# Esp32_Base_Shield.net
KiCad netlist of a schematic drawn in EAGLE
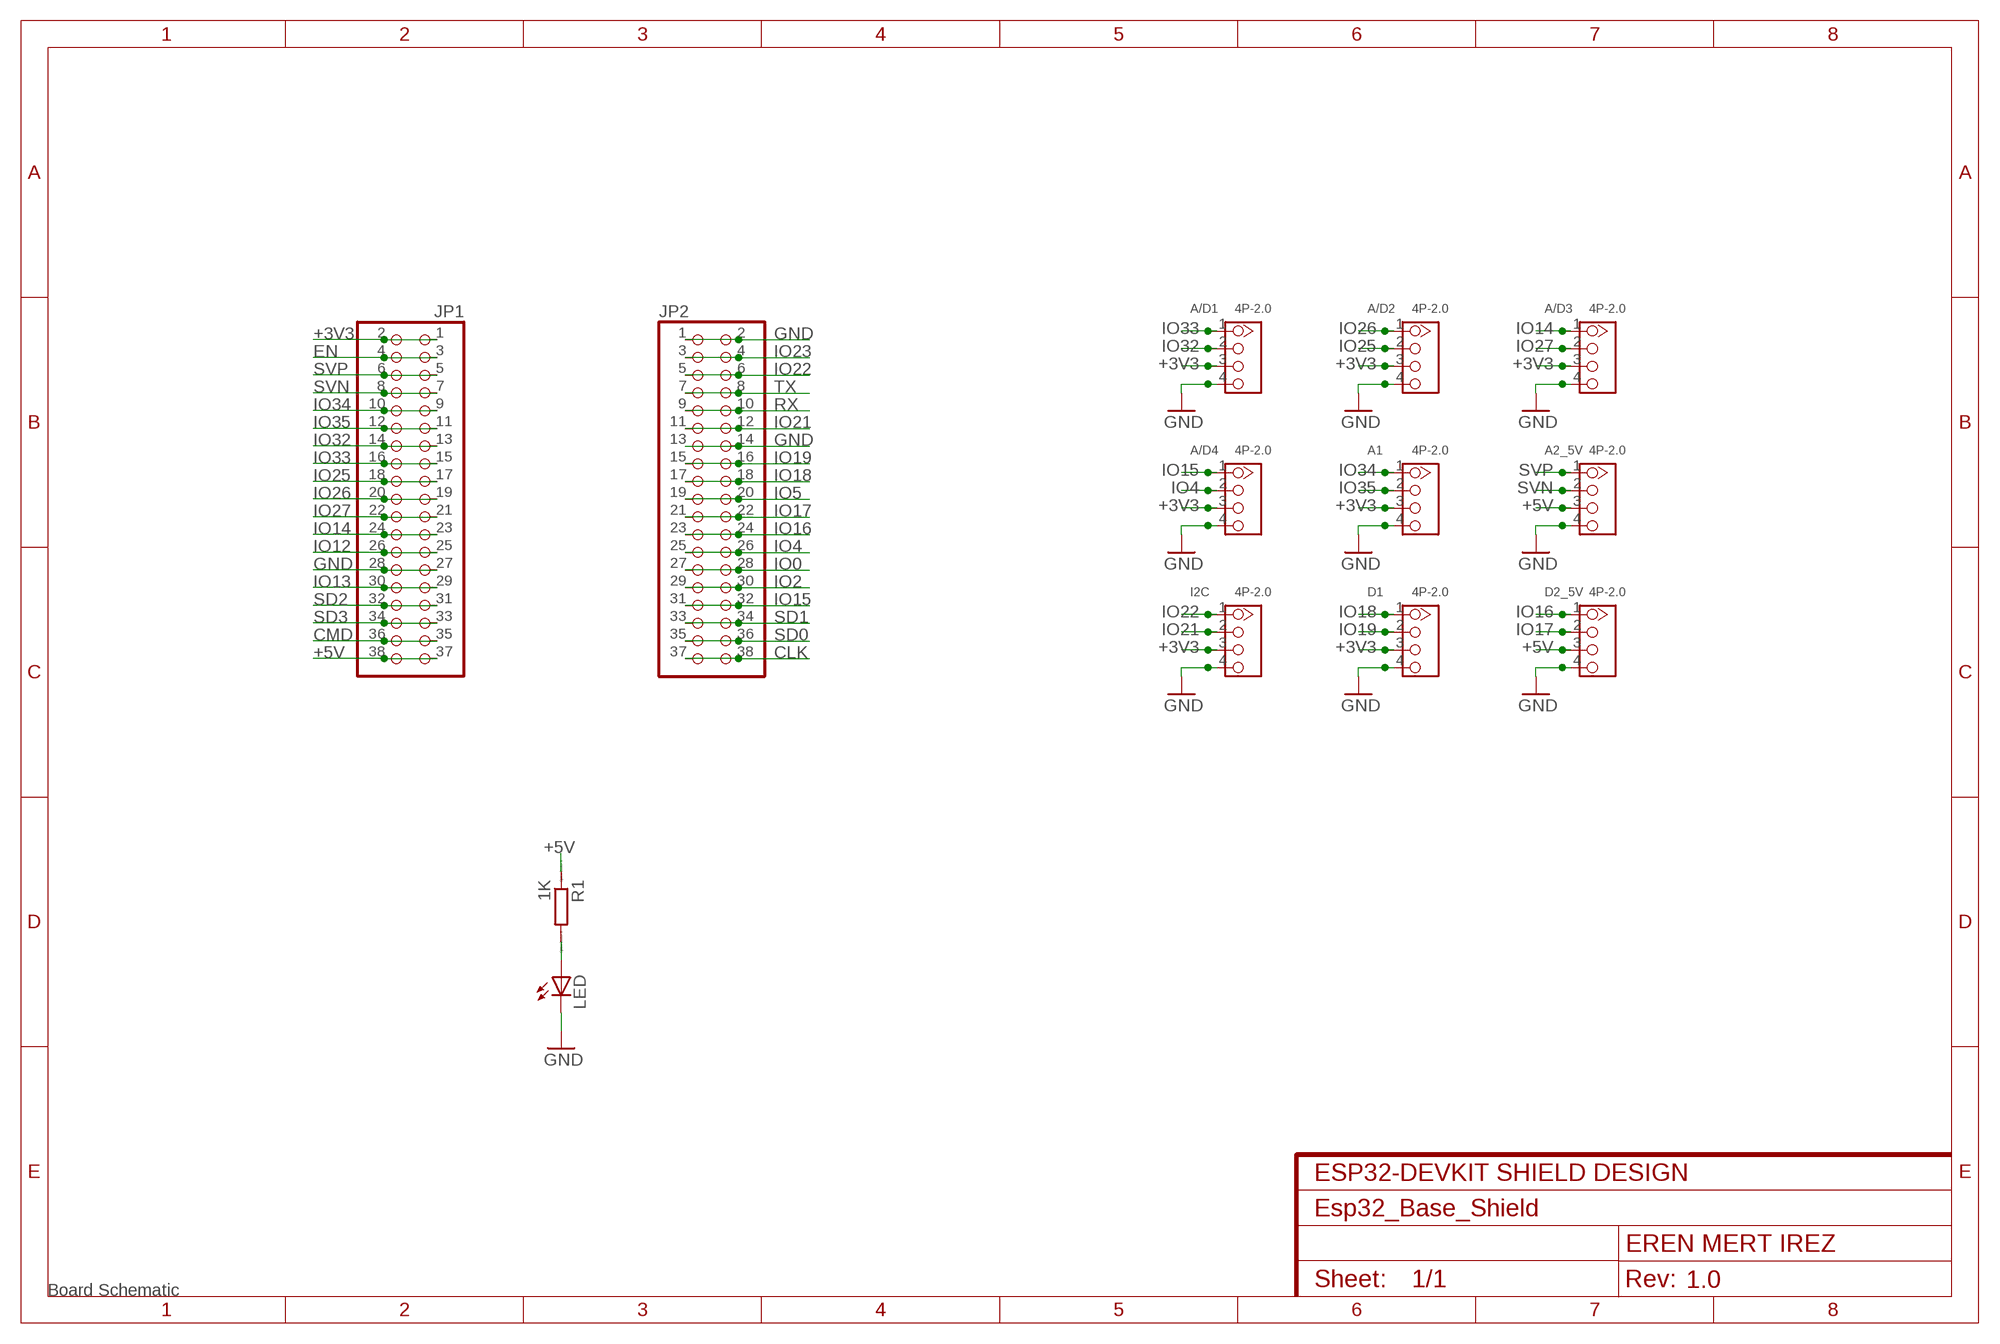
[diagram p0: schematic, sheet 1]

(export (version "E")
  (design (tool "Eeschema 10.0.6"))
  (components
    (comp (ref "A/D1")
      (value "4P-2.0")
      (footprint "eagle-import:HW4-2.0")
      (libsource (lib "eagle-import") (part "GROVE-CONNECTOR-DIP(4P-2.0)"))
    )
    (comp (ref "A/D2")
      (value "4P-2.0")
      (footprint "eagle-import:HW4-2.0")
      (libsource (lib "eagle-import") (part "GROVE-CONNECTOR-DIP(4P-2.0)"))
    )
    (comp (ref "A/D3")
      (value "4P-2.0")
      (footprint "eagle-import:HW4-2.0")
      (libsource (lib "eagle-import") (part "GROVE-CONNECTOR-DIP(4P-2.0)"))
    )
    (comp (ref "A/D4")
      (value "4P-2.0")
      (footprint "eagle-import:HW4-2.0")
      (libsource (lib "eagle-import") (part "GROVE-CONNECTOR-DIP(4P-2.0)"))
    )
    (comp (ref "A1")
      (value "4P-2.0")
      (footprint "eagle-import:HW4-2.0")
      (libsource (lib "eagle-import") (part "GROVE-CONNECTOR-DIP(4P-2.0)"))
    )
    (comp (ref "A2_5V")
      (value "4P-2.0")
      (footprint "eagle-import:HW4-2.0")
      (libsource (lib "eagle-import") (part "GROVE-CONNECTOR-DIP(4P-2.0)"))
    )
    (comp (ref "D1")
      (value "4P-2.0")
      (footprint "eagle-import:HW4-2.0")
      (libsource (lib "eagle-import") (part "GROVE-CONNECTOR-DIP(4P-2.0)"))
    )
    (comp (ref "D2_5V")
      (value "4P-2.0")
      (footprint "eagle-import:HW4-2.0")
      (libsource (lib "eagle-import") (part "GROVE-CONNECTOR-DIP(4P-2.0)"))
    )
    (comp (ref "I2C")
      (value "4P-2.0")
      (footprint "eagle-import:HW4-2.0")
      (libsource (lib "eagle-import") (part "GROVE-CONNECTOR-DIP(4P-2.0)"))
    )
    (comp (ref "JP1")
      (value "PINHD-2X19")
      (footprint "eagle-import:2X19")
      (libsource (lib "eagle-import") (part "PINHD-2X19"))
    )
    (comp (ref "JP2")
      (value "PINHD-2X19")
      (footprint "eagle-import:2X19")
      (libsource (lib "eagle-import") (part "PINHD-2X19"))
    )
    (comp (ref "LED")
      (value "LED3MM")
      (footprint "eagle-import:LED3MM")
      (libsource (lib "eagle-import") (part "LED3MM"))
    )
    (comp (ref "R1")
      (value "1K")
      (footprint "eagle-import:0207_10")
      (libsource (lib "eagle-import") (part "R0207/10"))
    )
  )
  (nets
    (net (code "1") (name "/+3V3") (class "Default")
      (node (ref "A/D1") (pin "3") (pinfunction "3_3") (pintype "bidirectional"))
      (node (ref "A/D2") (pin "3") (pinfunction "3_3") (pintype "bidirectional"))
      (node (ref "A/D3") (pin "3") (pinfunction "3_3") (pintype "bidirectional"))
      (node (ref "A/D4") (pin "3") (pinfunction "3_3") (pintype "bidirectional"))
      (node (ref "A1") (pin "3") (pinfunction "3_3") (pintype "bidirectional"))
      (node (ref "D1") (pin "3") (pinfunction "3_3") (pintype "bidirectional"))
      (node (ref "I2C") (pin "3") (pinfunction "3_3") (pintype "bidirectional"))
      (node (ref "JP1") (pin "1") (pinfunction "1_1") (pintype "passive"))
      (node (ref "JP1") (pin "2") (pinfunction "2_2") (pintype "passive"))
    )
    (net (code "2") (name "/+5V") (class "Default")
      (node (ref "A2_5V") (pin "3") (pinfunction "3_3") (pintype "bidirectional"))
      (node (ref "D2_5V") (pin "3") (pinfunction "3_3") (pintype "bidirectional"))
      (node (ref "JP1") (pin "37") (pinfunction "37_37") (pintype "passive"))
      (node (ref "JP1") (pin "38") (pinfunction "38_38") (pintype "passive"))
      (node (ref "R1") (pin "1") (pinfunction "1_1") (pintype "passive"))
    )
    (net (code "3") (name "/CLK") (class "Default")
      (node (ref "JP2") (pin "37") (pinfunction "37_37") (pintype "passive"))
      (node (ref "JP2") (pin "38") (pinfunction "38_38") (pintype "passive"))
    )
    (net (code "4") (name "/CMD") (class "Default")
      (node (ref "JP1") (pin "35") (pinfunction "35_35") (pintype "passive"))
      (node (ref "JP1") (pin "36") (pinfunction "36_36") (pintype "passive"))
    )
    (net (code "5") (name "/EN") (class "Default")
      (node (ref "JP1") (pin "3") (pinfunction "3_3") (pintype "passive"))
      (node (ref "JP1") (pin "4") (pinfunction "4_4") (pintype "passive"))
    )
    (net (code "6") (name "/IO0") (class "Default")
      (node (ref "JP2") (pin "27") (pinfunction "27_27") (pintype "passive"))
      (node (ref "JP2") (pin "28") (pinfunction "28_28") (pintype "passive"))
    )
    (net (code "7") (name "/IO2") (class "Default")
      (node (ref "JP2") (pin "29") (pinfunction "29_29") (pintype "passive"))
      (node (ref "JP2") (pin "30") (pinfunction "30_30") (pintype "passive"))
    )
    (net (code "8") (name "/IO4") (class "Default")
      (node (ref "A/D4") (pin "2") (pinfunction "2_2") (pintype "bidirectional"))
      (node (ref "JP2") (pin "25") (pinfunction "25_25") (pintype "passive"))
      (node (ref "JP2") (pin "26") (pinfunction "26_26") (pintype "passive"))
    )
    (net (code "9") (name "/IO5") (class "Default")
      (node (ref "JP2") (pin "19") (pinfunction "19_19") (pintype "passive"))
      (node (ref "JP2") (pin "20") (pinfunction "20_20") (pintype "passive"))
    )
    (net (code "10") (name "/IO12") (class "Default")
      (node (ref "JP1") (pin "25") (pinfunction "25_25") (pintype "passive"))
      (node (ref "JP1") (pin "26") (pinfunction "26_26") (pintype "passive"))
    )
    (net (code "11") (name "/IO13") (class "Default")
      (node (ref "JP1") (pin "29") (pinfunction "29_29") (pintype "passive"))
      (node (ref "JP1") (pin "30") (pinfunction "30_30") (pintype "passive"))
    )
    (net (code "12") (name "/IO14") (class "Default")
      (node (ref "A/D3") (pin "1") (pinfunction "1_1") (pintype "bidirectional"))
      (node (ref "JP1") (pin "23") (pinfunction "23_23") (pintype "passive"))
      (node (ref "JP1") (pin "24") (pinfunction "24_24") (pintype "passive"))
    )
    (net (code "13") (name "/IO15") (class "Default")
      (node (ref "A/D4") (pin "1") (pinfunction "1_1") (pintype "bidirectional"))
      (node (ref "JP2") (pin "31") (pinfunction "31_31") (pintype "passive"))
      (node (ref "JP2") (pin "32") (pinfunction "32_32") (pintype "passive"))
    )
    (net (code "14") (name "/IO16") (class "Default")
      (node (ref "D2_5V") (pin "1") (pinfunction "1_1") (pintype "bidirectional"))
      (node (ref "JP2") (pin "23") (pinfunction "23_23") (pintype "passive"))
      (node (ref "JP2") (pin "24") (pinfunction "24_24") (pintype "passive"))
    )
    (net (code "15") (name "/IO17") (class "Default")
      (node (ref "D2_5V") (pin "2") (pinfunction "2_2") (pintype "bidirectional"))
      (node (ref "JP2") (pin "21") (pinfunction "21_21") (pintype "passive"))
      (node (ref "JP2") (pin "22") (pinfunction "22_22") (pintype "passive"))
    )
    (net (code "16") (name "/IO18") (class "Default")
      (node (ref "D1") (pin "1") (pinfunction "1_1") (pintype "bidirectional"))
      (node (ref "JP2") (pin "17") (pinfunction "17_17") (pintype "passive"))
      (node (ref "JP2") (pin "18") (pinfunction "18_18") (pintype "passive"))
    )
    (net (code "17") (name "/IO19") (class "Default")
      (node (ref "D1") (pin "2") (pinfunction "2_2") (pintype "bidirectional"))
      (node (ref "JP2") (pin "15") (pinfunction "15_15") (pintype "passive"))
      (node (ref "JP2") (pin "16") (pinfunction "16_16") (pintype "passive"))
    )
    (net (code "18") (name "/IO21") (class "Default")
      (node (ref "I2C") (pin "2") (pinfunction "2_2") (pintype "bidirectional"))
      (node (ref "JP2") (pin "11") (pinfunction "11_11") (pintype "passive"))
      (node (ref "JP2") (pin "12") (pinfunction "12_12") (pintype "passive"))
    )
    (net (code "19") (name "/IO22") (class "Default")
      (node (ref "I2C") (pin "1") (pinfunction "1_1") (pintype "bidirectional"))
      (node (ref "JP2") (pin "5") (pinfunction "5_5") (pintype "passive"))
      (node (ref "JP2") (pin "6") (pinfunction "6_6") (pintype "passive"))
    )
    (net (code "20") (name "/IO23") (class "Default")
      (node (ref "JP2") (pin "3") (pinfunction "3_3") (pintype "passive"))
      (node (ref "JP2") (pin "4") (pinfunction "4_4") (pintype "passive"))
    )
    (net (code "21") (name "/IO25") (class "Default")
      (node (ref "A/D2") (pin "2") (pinfunction "2_2") (pintype "bidirectional"))
      (node (ref "JP1") (pin "17") (pinfunction "17_17") (pintype "passive"))
      (node (ref "JP1") (pin "18") (pinfunction "18_18") (pintype "passive"))
    )
    (net (code "22") (name "/IO26") (class "Default")
      (node (ref "A/D2") (pin "1") (pinfunction "1_1") (pintype "bidirectional"))
      (node (ref "JP1") (pin "19") (pinfunction "19_19") (pintype "passive"))
      (node (ref "JP1") (pin "20") (pinfunction "20_20") (pintype "passive"))
    )
    (net (code "23") (name "/IO27") (class "Default")
      (node (ref "A/D3") (pin "2") (pinfunction "2_2") (pintype "bidirectional"))
      (node (ref "JP1") (pin "21") (pinfunction "21_21") (pintype "passive"))
      (node (ref "JP1") (pin "22") (pinfunction "22_22") (pintype "passive"))
    )
    (net (code "24") (name "/IO32") (class "Default")
      (node (ref "A/D1") (pin "2") (pinfunction "2_2") (pintype "bidirectional"))
      (node (ref "JP1") (pin "13") (pinfunction "13_13") (pintype "passive"))
      (node (ref "JP1") (pin "14") (pinfunction "14_14") (pintype "passive"))
    )
    (net (code "25") (name "/IO33") (class "Default")
      (node (ref "A/D1") (pin "1") (pinfunction "1_1") (pintype "bidirectional"))
      (node (ref "JP1") (pin "15") (pinfunction "15_15") (pintype "passive"))
      (node (ref "JP1") (pin "16") (pinfunction "16_16") (pintype "passive"))
    )
    (net (code "26") (name "/IO34") (class "Default")
      (node (ref "A1") (pin "1") (pinfunction "1_1") (pintype "bidirectional"))
      (node (ref "JP1") (pin "10") (pinfunction "10_10") (pintype "passive"))
      (node (ref "JP1") (pin "9") (pinfunction "9_9") (pintype "passive"))
    )
    (net (code "27") (name "/IO35") (class "Default")
      (node (ref "A1") (pin "2") (pinfunction "2_2") (pintype "bidirectional"))
      (node (ref "JP1") (pin "11") (pinfunction "11_11") (pintype "passive"))
      (node (ref "JP1") (pin "12") (pinfunction "12_12") (pintype "passive"))
    )
    (net (code "28") (name "/RX") (class "Default")
      (node (ref "JP2") (pin "10") (pinfunction "10_10") (pintype "passive"))
      (node (ref "JP2") (pin "9") (pinfunction "9_9") (pintype "passive"))
    )
    (net (code "29") (name "/SD0") (class "Default")
      (node (ref "JP2") (pin "35") (pinfunction "35_35") (pintype "passive"))
      (node (ref "JP2") (pin "36") (pinfunction "36_36") (pintype "passive"))
    )
    (net (code "30") (name "/SD1") (class "Default")
      (node (ref "JP2") (pin "33") (pinfunction "33_33") (pintype "passive"))
      (node (ref "JP2") (pin "34") (pinfunction "34_34") (pintype "passive"))
    )
    (net (code "31") (name "/SD2") (class "Default")
      (node (ref "JP1") (pin "31") (pinfunction "31_31") (pintype "passive"))
      (node (ref "JP1") (pin "32") (pinfunction "32_32") (pintype "passive"))
    )
    (net (code "32") (name "/SD3") (class "Default")
      (node (ref "JP1") (pin "33") (pinfunction "33_33") (pintype "passive"))
      (node (ref "JP1") (pin "34") (pinfunction "34_34") (pintype "passive"))
    )
    (net (code "33") (name "/SVN") (class "Default")
      (node (ref "A2_5V") (pin "2") (pinfunction "2_2") (pintype "bidirectional"))
      (node (ref "JP1") (pin "7") (pinfunction "7_7") (pintype "passive"))
      (node (ref "JP1") (pin "8") (pinfunction "8_8") (pintype "passive"))
    )
    (net (code "34") (name "/SVP") (class "Default")
      (node (ref "A2_5V") (pin "1") (pinfunction "1_1") (pintype "bidirectional"))
      (node (ref "JP1") (pin "5") (pinfunction "5_5") (pintype "passive"))
      (node (ref "JP1") (pin "6") (pinfunction "6_6") (pintype "passive"))
    )
    (net (code "35") (name "/TX") (class "Default")
      (node (ref "JP2") (pin "7") (pinfunction "7_7") (pintype "passive"))
      (node (ref "JP2") (pin "8") (pinfunction "8_8") (pintype "passive"))
    )
    (net (code "36") (name "GND") (class "Default")
      (node (ref "A/D1") (pin "4") (pinfunction "4_4") (pintype "bidirectional"))
      (node (ref "A/D2") (pin "4") (pinfunction "4_4") (pintype "bidirectional"))
      (node (ref "A/D3") (pin "4") (pinfunction "4_4") (pintype "bidirectional"))
      (node (ref "A/D4") (pin "4") (pinfunction "4_4") (pintype "bidirectional"))
      (node (ref "A1") (pin "4") (pinfunction "4_4") (pintype "bidirectional"))
      (node (ref "A2_5V") (pin "4") (pinfunction "4_4") (pintype "bidirectional"))
      (node (ref "D1") (pin "4") (pinfunction "4_4") (pintype "bidirectional"))
      (node (ref "D2_5V") (pin "4") (pinfunction "4_4") (pintype "bidirectional"))
      (node (ref "I2C") (pin "4") (pinfunction "4_4") (pintype "bidirectional"))
      (node (ref "JP1") (pin "27") (pinfunction "27_27") (pintype "passive"))
      (node (ref "JP1") (pin "28") (pinfunction "28_28") (pintype "passive"))
      (node (ref "JP2") (pin "1") (pinfunction "1_1") (pintype "passive"))
      (node (ref "JP2") (pin "13") (pinfunction "13_13") (pintype "passive"))
      (node (ref "JP2") (pin "14") (pinfunction "14_14") (pintype "passive"))
      (node (ref "JP2") (pin "2") (pinfunction "2_2") (pintype "passive"))
      (node (ref "LED") (pin "K") (pinfunction "C_K") (pintype "passive"))
    )
    (net (code "37") (name "Net-(LED-PadA)") (class "Default")
      (node (ref "LED") (pin "A") (pinfunction "A_A") (pintype "passive"))
      (node (ref "R1") (pin "2") (pinfunction "2_2") (pintype "passive"))
    )
  )
)
